# STM32_ACTUADORES.net
KiCad netlist of a schematic drawn in EAGLE
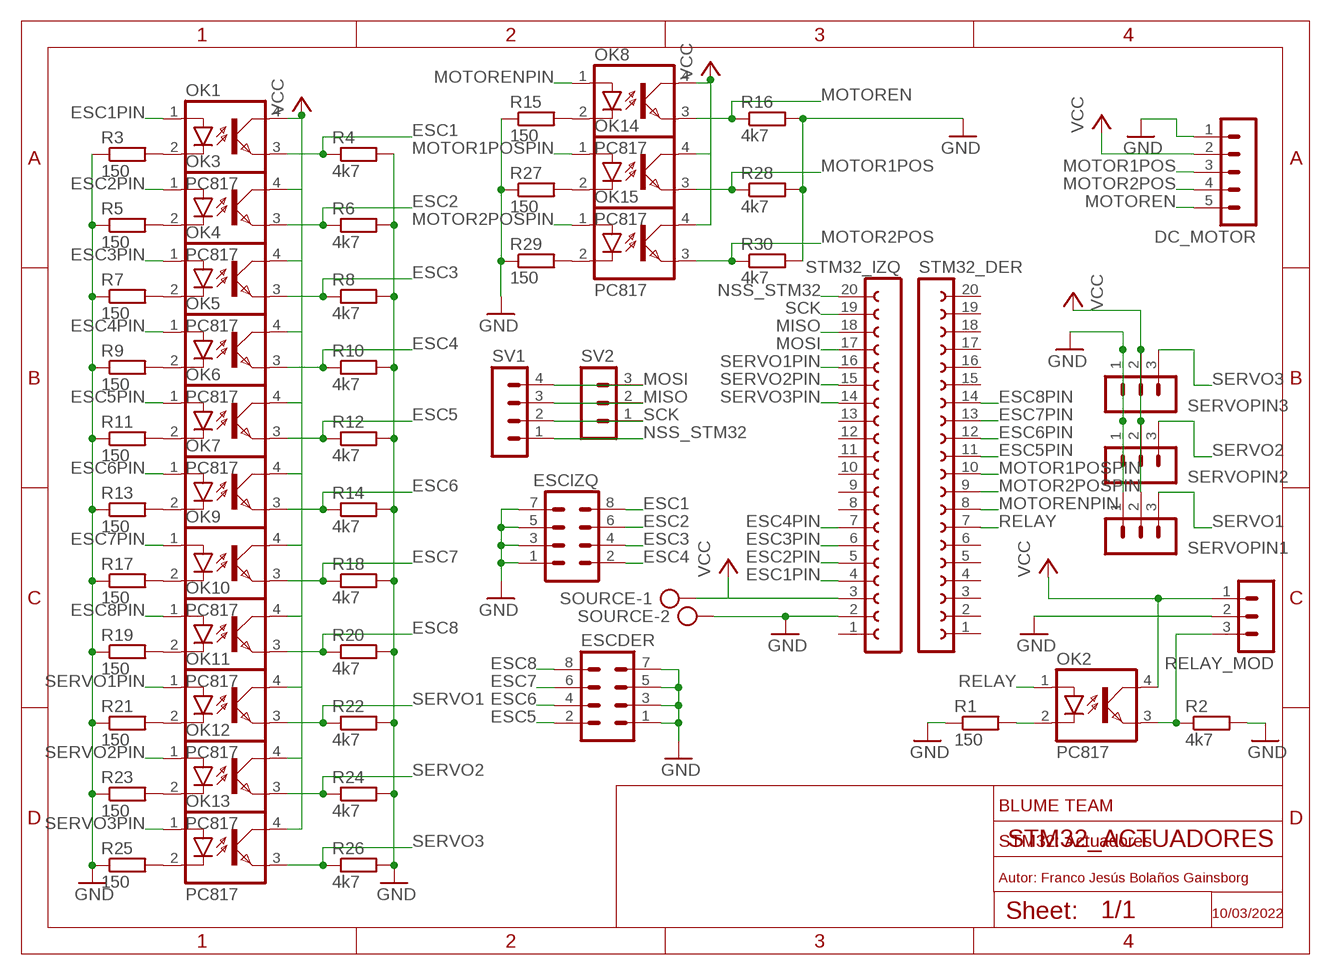
[diagram p0: schematic, sheet 1]

(export (version "E")
  (design (tool "Eeschema 10.0.6"))
  (components
    (comp (ref "DC_MOTOR")
      (value "MA05-1")
      (footprint "eagle-import:MA05-1")
      (libsource (lib "eagle-import") (part "MA05-1"))
    )
    (comp (ref "ESCDER")
      (value "MA04-2")
      (footprint "eagle-import:MA04-2")
      (libsource (lib "eagle-import") (part "MA04-2"))
    )
    (comp (ref "ESCIZQ")
      (value "MA04-2")
      (footprint "eagle-import:MA04-2")
      (libsource (lib "eagle-import") (part "MA04-2"))
    )
    (comp (ref "OK1")
      (value "PC817")
      (footprint "eagle-import:DIL04")
      (fields (field (name "MPN") "PC817X4J000F"))
      (libsource (lib "eagle-import") (part "PC817"))
    )
    (comp (ref "OK2")
      (value "PC817")
      (footprint "eagle-import:DIL04")
      (fields (field (name "MPN") "PC817X4J000F"))
      (libsource (lib "eagle-import") (part "PC817"))
    )
    (comp (ref "OK3")
      (value "PC817")
      (footprint "eagle-import:DIL04")
      (fields (field (name "MPN") "PC817X4J000F"))
      (libsource (lib "eagle-import") (part "PC817"))
    )
    (comp (ref "OK4")
      (value "PC817")
      (footprint "eagle-import:DIL04")
      (fields (field (name "MPN") "PC817X4J000F"))
      (libsource (lib "eagle-import") (part "PC817"))
    )
    (comp (ref "OK5")
      (value "PC817")
      (footprint "eagle-import:DIL04")
      (fields (field (name "MPN") "PC817X4J000F"))
      (libsource (lib "eagle-import") (part "PC817"))
    )
    (comp (ref "OK6")
      (value "PC817")
      (footprint "eagle-import:DIL04")
      (fields (field (name "MPN") "PC817X4J000F"))
      (libsource (lib "eagle-import") (part "PC817"))
    )
    (comp (ref "OK7")
      (value "PC817")
      (footprint "eagle-import:DIL04")
      (fields (field (name "MPN") "PC817X4J000F"))
      (libsource (lib "eagle-import") (part "PC817"))
    )
    (comp (ref "OK8")
      (value "PC817")
      (footprint "eagle-import:DIL04")
      (fields (field (name "MPN") "PC817X4J000F"))
      (libsource (lib "eagle-import") (part "PC817"))
    )
    (comp (ref "OK9")
      (value "PC817")
      (footprint "eagle-import:DIL04")
      (fields (field (name "MPN") "PC817X4J000F"))
      (libsource (lib "eagle-import") (part "PC817"))
    )
    (comp (ref "OK10")
      (value "PC817")
      (footprint "eagle-import:DIL04")
      (fields (field (name "MPN") "PC817X4J000F"))
      (libsource (lib "eagle-import") (part "PC817"))
    )
    (comp (ref "OK11")
      (value "PC817")
      (footprint "eagle-import:DIL04")
      (fields (field (name "MPN") "PC817X4J000F"))
      (libsource (lib "eagle-import") (part "PC817"))
    )
    (comp (ref "OK12")
      (value "PC817")
      (footprint "eagle-import:DIL04")
      (fields (field (name "MPN") "PC817X4J000F"))
      (libsource (lib "eagle-import") (part "PC817"))
    )
    (comp (ref "OK13")
      (value "PC817")
      (footprint "eagle-import:DIL04")
      (fields (field (name "MPN") "PC817X4J000F"))
      (libsource (lib "eagle-import") (part "PC817"))
    )
    (comp (ref "OK14")
      (value "PC817")
      (footprint "eagle-import:DIL04")
      (fields (field (name "MPN") "PC817X4J000F"))
      (libsource (lib "eagle-import") (part "PC817"))
    )
    (comp (ref "OK15")
      (value "PC817")
      (footprint "eagle-import:DIL04")
      (fields (field (name "MPN") "PC817X4J000F"))
      (libsource (lib "eagle-import") (part "PC817"))
    )
    (comp (ref "R1")
      (value "150")
      (footprint "eagle-import:0207_10")
      (libsource (lib "eagle-import") (part "R-EU_0207/10"))
    )
    (comp (ref "R2")
      (value "4k7")
      (footprint "eagle-import:0207_10")
      (libsource (lib "eagle-import") (part "R-EU_0207/10"))
    )
    (comp (ref "R3")
      (value "150")
      (footprint "eagle-import:0207_10")
      (libsource (lib "eagle-import") (part "R-EU_0207/10"))
    )
    (comp (ref "R4")
      (value "4k7")
      (footprint "eagle-import:0207_10")
      (libsource (lib "eagle-import") (part "R-EU_0207/10"))
    )
    (comp (ref "R5")
      (value "150")
      (footprint "eagle-import:0207_10")
      (libsource (lib "eagle-import") (part "R-EU_0207/10"))
    )
    (comp (ref "R6")
      (value "4k7")
      (footprint "eagle-import:0207_10")
      (libsource (lib "eagle-import") (part "R-EU_0207/10"))
    )
    (comp (ref "R7")
      (value "150")
      (footprint "eagle-import:0207_10")
      (libsource (lib "eagle-import") (part "R-EU_0207/10"))
    )
    (comp (ref "R8")
      (value "4k7")
      (footprint "eagle-import:0207_10")
      (libsource (lib "eagle-import") (part "R-EU_0207/10"))
    )
    (comp (ref "R9")
      (value "150")
      (footprint "eagle-import:0207_10")
      (libsource (lib "eagle-import") (part "R-EU_0207/10"))
    )
    (comp (ref "R10")
      (value "4k7")
      (footprint "eagle-import:0207_10")
      (libsource (lib "eagle-import") (part "R-EU_0207/10"))
    )
    (comp (ref "R11")
      (value "150")
      (footprint "eagle-import:0207_10")
      (libsource (lib "eagle-import") (part "R-EU_0207/10"))
    )
    (comp (ref "R12")
      (value "4k7")
      (footprint "eagle-import:0207_10")
      (libsource (lib "eagle-import") (part "R-EU_0207/10"))
    )
    (comp (ref "R13")
      (value "150")
      (footprint "eagle-import:0207_10")
      (libsource (lib "eagle-import") (part "R-EU_0207/10"))
    )
    (comp (ref "R14")
      (value "4k7")
      (footprint "eagle-import:0207_10")
      (libsource (lib "eagle-import") (part "R-EU_0207/10"))
    )
    (comp (ref "R15")
      (value "150")
      (footprint "eagle-import:0207_10")
      (libsource (lib "eagle-import") (part "R-EU_0207/10"))
    )
    (comp (ref "R16")
      (value "4k7")
      (footprint "eagle-import:0207_10")
      (libsource (lib "eagle-import") (part "R-EU_0207/10"))
    )
    (comp (ref "R17")
      (value "150")
      (footprint "eagle-import:0207_10")
      (libsource (lib "eagle-import") (part "R-EU_0207/10"))
    )
    (comp (ref "R18")
      (value "4k7")
      (footprint "eagle-import:0207_10")
      (libsource (lib "eagle-import") (part "R-EU_0207/10"))
    )
    (comp (ref "R19")
      (value "150")
      (footprint "eagle-import:0207_10")
      (libsource (lib "eagle-import") (part "R-EU_0207/10"))
    )
    (comp (ref "R20")
      (value "4k7")
      (footprint "eagle-import:0207_10")
      (libsource (lib "eagle-import") (part "R-EU_0207/10"))
    )
    (comp (ref "R21")
      (value "150")
      (footprint "eagle-import:0207_10")
      (libsource (lib "eagle-import") (part "R-EU_0207/10"))
    )
    (comp (ref "R22")
      (value "4k7")
      (footprint "eagle-import:0207_10")
      (libsource (lib "eagle-import") (part "R-EU_0207/10"))
    )
    (comp (ref "R23")
      (value "150")
      (footprint "eagle-import:0207_10")
      (libsource (lib "eagle-import") (part "R-EU_0207/10"))
    )
    (comp (ref "R24")
      (value "4k7")
      (footprint "eagle-import:0207_10")
      (libsource (lib "eagle-import") (part "R-EU_0207/10"))
    )
    (comp (ref "R25")
      (value "150")
      (footprint "eagle-import:0207_10")
      (libsource (lib "eagle-import") (part "R-EU_0207/10"))
    )
    (comp (ref "R26")
      (value "4k7")
      (footprint "eagle-import:0207_10")
      (libsource (lib "eagle-import") (part "R-EU_0207/10"))
    )
    (comp (ref "R27")
      (value "150")
      (footprint "eagle-import:0207_10")
      (libsource (lib "eagle-import") (part "R-EU_0207/10"))
    )
    (comp (ref "R28")
      (value "4k7")
      (footprint "eagle-import:0207_10")
      (libsource (lib "eagle-import") (part "R-EU_0207/10"))
    )
    (comp (ref "R29")
      (value "150")
      (footprint "eagle-import:0207_10")
      (libsource (lib "eagle-import") (part "R-EU_0207/10"))
    )
    (comp (ref "R30")
      (value "4k7")
      (footprint "eagle-import:0207_10")
      (libsource (lib "eagle-import") (part "R-EU_0207/10"))
    )
    (comp (ref "RELAY_MOD")
      (value "MA03-1")
      (footprint "eagle-import:MA03-1")
      (libsource (lib "eagle-import") (part "MA03-1"))
    )
    (comp (ref "SERVOPIN1")
      (value "MA03-1")
      (footprint "eagle-import:MA03-1")
      (libsource (lib "eagle-import") (part "MA03-1"))
    )
    (comp (ref "SERVOPIN2")
      (value "MA03-1")
      (footprint "eagle-import:MA03-1")
      (libsource (lib "eagle-import") (part "MA03-1"))
    )
    (comp (ref "SERVOPIN3")
      (value "MA03-1")
      (footprint "eagle-import:MA03-1")
      (libsource (lib "eagle-import") (part "MA03-1"))
    )
    (comp (ref "SOURCE")
      (value "AK300/2")
      (footprint "eagle-import:AK300_2")
      (libsource (lib "eagle-import") (part "AK300/2"))
    )
    (comp (ref "STM32_DER")
      (value "FE20-1")
      (footprint "eagle-import:FE20")
      (libsource (lib "eagle-import") (part "FE20-1"))
    )
    (comp (ref "STM32_IZQ")
      (value "FE20-1")
      (footprint "eagle-import:FE20")
      (libsource (lib "eagle-import") (part "FE20-1"))
    )
    (comp (ref "SV1")
      (value "MA04-1")
      (footprint "eagle-import:MA04-1")
      (libsource (lib "eagle-import") (part "MA04-1"))
    )
    (comp (ref "SV2")
      (value "MA03-1")
      (footprint "eagle-import:MA03-1")
      (libsource (lib "eagle-import") (part "MA03-1"))
    )
  )
  (nets
    (net (code "1") (name "/ESC1") (class "Default")
      (node (ref "ESCIZQ") (pin "8") (pinfunction "8_8") (pintype "passive"))
      (node (ref "OK1") (pin "3") (pinfunction "EMIT_3") (pintype "passive"))
      (node (ref "R4") (pin "1") (pinfunction "1_1") (pintype "passive"))
    )
    (net (code "2") (name "/ESC1PIN") (class "Default")
      (node (ref "OK1") (pin "1") (pinfunction "A_1") (pintype "passive"))
      (node (ref "STM32_IZQ") (pin "4") (pinfunction "4_4") (pintype "passive"))
    )
    (net (code "3") (name "/ESC2") (class "Default")
      (node (ref "ESCIZQ") (pin "6") (pinfunction "6_6") (pintype "passive"))
      (node (ref "OK3") (pin "3") (pinfunction "EMIT_3") (pintype "passive"))
      (node (ref "R6") (pin "1") (pinfunction "1_1") (pintype "passive"))
    )
    (net (code "4") (name "/ESC2PIN") (class "Default")
      (node (ref "OK3") (pin "1") (pinfunction "A_1") (pintype "passive"))
      (node (ref "STM32_IZQ") (pin "5") (pinfunction "5_5") (pintype "passive"))
    )
    (net (code "5") (name "/ESC3") (class "Default")
      (node (ref "ESCIZQ") (pin "4") (pinfunction "4_4") (pintype "passive"))
      (node (ref "OK4") (pin "3") (pinfunction "EMIT_3") (pintype "passive"))
      (node (ref "R8") (pin "1") (pinfunction "1_1") (pintype "passive"))
    )
    (net (code "6") (name "/ESC3PIN") (class "Default")
      (node (ref "OK4") (pin "1") (pinfunction "A_1") (pintype "passive"))
      (node (ref "STM32_IZQ") (pin "6") (pinfunction "6_6") (pintype "passive"))
    )
    (net (code "7") (name "/ESC4") (class "Default")
      (node (ref "ESCIZQ") (pin "2") (pinfunction "2_2") (pintype "passive"))
      (node (ref "OK5") (pin "3") (pinfunction "EMIT_3") (pintype "passive"))
      (node (ref "R10") (pin "1") (pinfunction "1_1") (pintype "passive"))
    )
    (net (code "8") (name "/ESC4PIN") (class "Default")
      (node (ref "OK5") (pin "1") (pinfunction "A_1") (pintype "passive"))
      (node (ref "STM32_IZQ") (pin "7") (pinfunction "7_7") (pintype "passive"))
    )
    (net (code "9") (name "/ESC5") (class "Default")
      (node (ref "ESCDER") (pin "2") (pinfunction "2_2") (pintype "passive"))
      (node (ref "OK6") (pin "3") (pinfunction "EMIT_3") (pintype "passive"))
      (node (ref "R12") (pin "1") (pinfunction "1_1") (pintype "passive"))
    )
    (net (code "10") (name "/ESC5PIN") (class "Default")
      (node (ref "OK6") (pin "1") (pinfunction "A_1") (pintype "passive"))
      (node (ref "STM32_DER") (pin "11") (pinfunction "11_11") (pintype "passive"))
    )
    (net (code "11") (name "/ESC6") (class "Default")
      (node (ref "ESCDER") (pin "4") (pinfunction "4_4") (pintype "passive"))
      (node (ref "OK7") (pin "3") (pinfunction "EMIT_3") (pintype "passive"))
      (node (ref "R14") (pin "1") (pinfunction "1_1") (pintype "passive"))
    )
    (net (code "12") (name "/ESC6PIN") (class "Default")
      (node (ref "OK7") (pin "1") (pinfunction "A_1") (pintype "passive"))
      (node (ref "STM32_DER") (pin "12") (pinfunction "12_12") (pintype "passive"))
    )
    (net (code "13") (name "/ESC7") (class "Default")
      (node (ref "ESCDER") (pin "6") (pinfunction "6_6") (pintype "passive"))
      (node (ref "OK9") (pin "3") (pinfunction "EMIT_3") (pintype "passive"))
      (node (ref "R18") (pin "1") (pinfunction "1_1") (pintype "passive"))
    )
    (net (code "14") (name "/ESC7PIN") (class "Default")
      (node (ref "OK9") (pin "1") (pinfunction "A_1") (pintype "passive"))
      (node (ref "STM32_DER") (pin "13") (pinfunction "13_13") (pintype "passive"))
    )
    (net (code "15") (name "/ESC8") (class "Default")
      (node (ref "ESCDER") (pin "8") (pinfunction "8_8") (pintype "passive"))
      (node (ref "OK10") (pin "3") (pinfunction "EMIT_3") (pintype "passive"))
      (node (ref "R20") (pin "1") (pinfunction "1_1") (pintype "passive"))
    )
    (net (code "16") (name "/ESC8PIN") (class "Default")
      (node (ref "OK10") (pin "1") (pinfunction "A_1") (pintype "passive"))
      (node (ref "STM32_DER") (pin "14") (pinfunction "14_14") (pintype "passive"))
    )
    (net (code "17") (name "/MISO") (class "Default")
      (node (ref "STM32_IZQ") (pin "18") (pinfunction "18_18") (pintype "passive"))
      (node (ref "SV1") (pin "3") (pinfunction "3_3") (pintype "passive"))
      (node (ref "SV2") (pin "2") (pinfunction "2_2") (pintype "passive"))
    )
    (net (code "18") (name "/MOSI") (class "Default")
      (node (ref "STM32_IZQ") (pin "17") (pinfunction "17_17") (pintype "passive"))
      (node (ref "SV1") (pin "4") (pinfunction "4_4") (pintype "passive"))
      (node (ref "SV2") (pin "3") (pinfunction "3_3") (pintype "passive"))
    )
    (net (code "19") (name "/MOTOR1POS") (class "Default")
      (node (ref "DC_MOTOR") (pin "3") (pinfunction "3_3") (pintype "passive"))
      (node (ref "OK14") (pin "3") (pinfunction "EMIT_3") (pintype "passive"))
      (node (ref "R28") (pin "1") (pinfunction "1_1") (pintype "passive"))
    )
    (net (code "20") (name "/MOTOR1POSPIN") (class "Default")
      (node (ref "OK14") (pin "1") (pinfunction "A_1") (pintype "passive"))
      (node (ref "STM32_DER") (pin "10") (pinfunction "10_10") (pintype "passive"))
    )
    (net (code "21") (name "/MOTOR2POS") (class "Default")
      (node (ref "DC_MOTOR") (pin "4") (pinfunction "4_4") (pintype "passive"))
      (node (ref "OK15") (pin "3") (pinfunction "EMIT_3") (pintype "passive"))
      (node (ref "R30") (pin "1") (pinfunction "1_1") (pintype "passive"))
    )
    (net (code "22") (name "/MOTOR2POSPIN") (class "Default")
      (node (ref "OK15") (pin "1") (pinfunction "A_1") (pintype "passive"))
      (node (ref "STM32_DER") (pin "9") (pinfunction "9_9") (pintype "passive"))
    )
    (net (code "23") (name "/MOTOREN") (class "Default")
      (node (ref "DC_MOTOR") (pin "5") (pinfunction "5_5") (pintype "passive"))
      (node (ref "OK8") (pin "3") (pinfunction "EMIT_3") (pintype "passive"))
      (node (ref "R16") (pin "1") (pinfunction "1_1") (pintype "passive"))
    )
    (net (code "24") (name "/MOTORENPIN") (class "Default")
      (node (ref "OK8") (pin "1") (pinfunction "A_1") (pintype "passive"))
      (node (ref "STM32_DER") (pin "8") (pinfunction "8_8") (pintype "passive"))
    )
    (net (code "25") (name "/NSS_STM32") (class "Default")
      (node (ref "STM32_IZQ") (pin "20") (pinfunction "20_20") (pintype "passive"))
      (node (ref "SV1") (pin "1") (pinfunction "1_1") (pintype "passive"))
    )
    (net (code "26") (name "/RELAY") (class "Default")
      (node (ref "OK2") (pin "1") (pinfunction "A_1") (pintype "passive"))
      (node (ref "STM32_DER") (pin "7") (pinfunction "7_7") (pintype "passive"))
    )
    (net (code "27") (name "/SCK") (class "Default")
      (node (ref "STM32_IZQ") (pin "19") (pinfunction "19_19") (pintype "passive"))
      (node (ref "SV1") (pin "2") (pinfunction "2_2") (pintype "passive"))
      (node (ref "SV2") (pin "1") (pinfunction "1_1") (pintype "passive"))
    )
    (net (code "28") (name "/SERVO1") (class "Default")
      (node (ref "OK11") (pin "3") (pinfunction "EMIT_3") (pintype "passive"))
      (node (ref "R22") (pin "1") (pinfunction "1_1") (pintype "passive"))
      (node (ref "SERVOPIN1") (pin "3") (pinfunction "3_3") (pintype "passive"))
    )
    (net (code "29") (name "/SERVO1PIN") (class "Default")
      (node (ref "OK11") (pin "1") (pinfunction "A_1") (pintype "passive"))
      (node (ref "STM32_IZQ") (pin "16") (pinfunction "16_16") (pintype "passive"))
    )
    (net (code "30") (name "/SERVO2") (class "Default")
      (node (ref "OK12") (pin "3") (pinfunction "EMIT_3") (pintype "passive"))
      (node (ref "R24") (pin "1") (pinfunction "1_1") (pintype "passive"))
      (node (ref "SERVOPIN2") (pin "3") (pinfunction "3_3") (pintype "passive"))
    )
    (net (code "31") (name "/SERVO2PIN") (class "Default")
      (node (ref "OK12") (pin "1") (pinfunction "A_1") (pintype "passive"))
      (node (ref "STM32_IZQ") (pin "15") (pinfunction "15_15") (pintype "passive"))
    )
    (net (code "32") (name "/SERVO3") (class "Default")
      (node (ref "OK13") (pin "3") (pinfunction "EMIT_3") (pintype "passive"))
      (node (ref "R26") (pin "1") (pinfunction "1_1") (pintype "passive"))
      (node (ref "SERVOPIN3") (pin "3") (pinfunction "3_3") (pintype "passive"))
    )
    (net (code "33") (name "/SERVO3PIN") (class "Default")
      (node (ref "OK13") (pin "1") (pinfunction "A_1") (pintype "passive"))
      (node (ref "STM32_IZQ") (pin "14") (pinfunction "14_14") (pintype "passive"))
    )
    (net (code "34") (name "GND") (class "Default")
      (node (ref "DC_MOTOR") (pin "1") (pinfunction "1_1") (pintype "passive"))
      (node (ref "ESCDER") (pin "1") (pinfunction "1_1") (pintype "passive"))
      (node (ref "ESCDER") (pin "3") (pinfunction "3_3") (pintype "passive"))
      (node (ref "ESCDER") (pin "5") (pinfunction "5_5") (pintype "passive"))
      (node (ref "ESCDER") (pin "7") (pinfunction "7_7") (pintype "passive"))
      (node (ref "ESCIZQ") (pin "1") (pinfunction "1_1") (pintype "passive"))
      (node (ref "ESCIZQ") (pin "3") (pinfunction "3_3") (pintype "passive"))
      (node (ref "ESCIZQ") (pin "5") (pinfunction "5_5") (pintype "passive"))
      (node (ref "ESCIZQ") (pin "7") (pinfunction "7_7") (pintype "passive"))
      (node (ref "R1") (pin "1") (pinfunction "1_1") (pintype "passive"))
      (node (ref "R10") (pin "2") (pinfunction "2_2") (pintype "passive"))
      (node (ref "R11") (pin "1") (pinfunction "1_1") (pintype "passive"))
      (node (ref "R12") (pin "2") (pinfunction "2_2") (pintype "passive"))
      (node (ref "R13") (pin "1") (pinfunction "1_1") (pintype "passive"))
      (node (ref "R14") (pin "2") (pinfunction "2_2") (pintype "passive"))
      (node (ref "R15") (pin "1") (pinfunction "1_1") (pintype "passive"))
      (node (ref "R16") (pin "2") (pinfunction "2_2") (pintype "passive"))
      (node (ref "R17") (pin "1") (pinfunction "1_1") (pintype "passive"))
      (node (ref "R18") (pin "2") (pinfunction "2_2") (pintype "passive"))
      (node (ref "R19") (pin "1") (pinfunction "1_1") (pintype "passive"))
      (node (ref "R2") (pin "2") (pinfunction "2_2") (pintype "passive"))
      (node (ref "R20") (pin "2") (pinfunction "2_2") (pintype "passive"))
      (node (ref "R21") (pin "1") (pinfunction "1_1") (pintype "passive"))
      (node (ref "R22") (pin "2") (pinfunction "2_2") (pintype "passive"))
      (node (ref "R23") (pin "1") (pinfunction "1_1") (pintype "passive"))
      (node (ref "R24") (pin "2") (pinfunction "2_2") (pintype "passive"))
      (node (ref "R25") (pin "1") (pinfunction "1_1") (pintype "passive"))
      (node (ref "R26") (pin "2") (pinfunction "2_2") (pintype "passive"))
      (node (ref "R27") (pin "1") (pinfunction "1_1") (pintype "passive"))
      (node (ref "R28") (pin "2") (pinfunction "2_2") (pintype "passive"))
      (node (ref "R29") (pin "1") (pinfunction "1_1") (pintype "passive"))
      (node (ref "R3") (pin "1") (pinfunction "1_1") (pintype "passive"))
      (node (ref "R30") (pin "2") (pinfunction "2_2") (pintype "passive"))
      (node (ref "R4") (pin "2") (pinfunction "2_2") (pintype "passive"))
      (node (ref "R5") (pin "1") (pinfunction "1_1") (pintype "passive"))
      (node (ref "R6") (pin "2") (pinfunction "2_2") (pintype "passive"))
      (node (ref "R7") (pin "1") (pinfunction "1_1") (pintype "passive"))
      (node (ref "R8") (pin "2") (pinfunction "2_2") (pintype "passive"))
      (node (ref "R9") (pin "1") (pinfunction "1_1") (pintype "passive"))
      (node (ref "RELAY_MOD") (pin "2") (pinfunction "2_2") (pintype "passive"))
      (node (ref "SERVOPIN1") (pin "1") (pinfunction "1_1") (pintype "passive"))
      (node (ref "SERVOPIN2") (pin "1") (pinfunction "1_1") (pintype "passive"))
      (node (ref "SERVOPIN3") (pin "1") (pinfunction "1_1") (pintype "passive"))
      (node (ref "SOURCE") (pin "2") (pinfunction "KL_2") (pintype "passive"))
      (node (ref "STM32_IZQ") (pin "2") (pinfunction "2_2") (pintype "passive"))
    )
    (net (code "35") (name "Net-(OK1-C)") (class "Default")
      (node (ref "OK1") (pin "2") (pinfunction "C_2") (pintype "passive"))
      (node (ref "R3") (pin "2") (pinfunction "2_2") (pintype "passive"))
    )
    (net (code "36") (name "Net-(OK2-C)") (class "Default")
      (node (ref "OK2") (pin "2") (pinfunction "C_2") (pintype "passive"))
      (node (ref "R1") (pin "2") (pinfunction "2_2") (pintype "passive"))
    )
    (net (code "37") (name "Net-(OK2-EMIT)") (class "Default")
      (node (ref "OK2") (pin "3") (pinfunction "EMIT_3") (pintype "passive"))
      (node (ref "R2") (pin "1") (pinfunction "1_1") (pintype "passive"))
      (node (ref "RELAY_MOD") (pin "3") (pinfunction "3_3") (pintype "passive"))
    )
    (net (code "38") (name "Net-(OK3-C)") (class "Default")
      (node (ref "OK3") (pin "2") (pinfunction "C_2") (pintype "passive"))
      (node (ref "R5") (pin "2") (pinfunction "2_2") (pintype "passive"))
    )
    (net (code "39") (name "Net-(OK4-C)") (class "Default")
      (node (ref "OK4") (pin "2") (pinfunction "C_2") (pintype "passive"))
      (node (ref "R7") (pin "2") (pinfunction "2_2") (pintype "passive"))
    )
    (net (code "40") (name "Net-(OK5-C)") (class "Default")
      (node (ref "OK5") (pin "2") (pinfunction "C_2") (pintype "passive"))
      (node (ref "R9") (pin "2") (pinfunction "2_2") (pintype "passive"))
    )
    (net (code "41") (name "Net-(OK6-C)") (class "Default")
      (node (ref "OK6") (pin "2") (pinfunction "C_2") (pintype "passive"))
      (node (ref "R11") (pin "2") (pinfunction "2_2") (pintype "passive"))
    )
    (net (code "42") (name "Net-(OK7-C)") (class "Default")
      (node (ref "OK7") (pin "2") (pinfunction "C_2") (pintype "passive"))
      (node (ref "R13") (pin "2") (pinfunction "2_2") (pintype "passive"))
    )
    (net (code "43") (name "Net-(OK8-C)") (class "Default")
      (node (ref "OK8") (pin "2") (pinfunction "C_2") (pintype "passive"))
      (node (ref "R15") (pin "2") (pinfunction "2_2") (pintype "passive"))
    )
    (net (code "44") (name "Net-(OK9-C)") (class "Default")
      (node (ref "OK9") (pin "2") (pinfunction "C_2") (pintype "passive"))
      (node (ref "R17") (pin "2") (pinfunction "2_2") (pintype "passive"))
    )
    (net (code "45") (name "Net-(OK10-C)") (class "Default")
      (node (ref "OK10") (pin "2") (pinfunction "C_2") (pintype "passive"))
      (node (ref "R19") (pin "2") (pinfunction "2_2") (pintype "passive"))
    )
    (net (code "46") (name "Net-(OK11-C)") (class "Default")
      (node (ref "OK11") (pin "2") (pinfunction "C_2") (pintype "passive"))
      (node (ref "R21") (pin "2") (pinfunction "2_2") (pintype "passive"))
    )
    (net (code "47") (name "Net-(OK12-C)") (class "Default")
      (node (ref "OK12") (pin "2") (pinfunction "C_2") (pintype "passive"))
      (node (ref "R23") (pin "2") (pinfunction "2_2") (pintype "passive"))
    )
    (net (code "48") (name "Net-(OK13-C)") (class "Default")
      (node (ref "OK13") (pin "2") (pinfunction "C_2") (pintype "passive"))
      (node (ref "R25") (pin "2") (pinfunction "2_2") (pintype "passive"))
    )
    (net (code "49") (name "Net-(OK14-C)") (class "Default")
      (node (ref "OK14") (pin "2") (pinfunction "C_2") (pintype "passive"))
      (node (ref "R27") (pin "2") (pinfunction "2_2") (pintype "passive"))
    )
    (net (code "50") (name "Net-(OK15-C)") (class "Default")
      (node (ref "OK15") (pin "2") (pinfunction "C_2") (pintype "passive"))
      (node (ref "R29") (pin "2") (pinfunction "2_2") (pintype "passive"))
    )
    (net (code "51") (name "VCC") (class "Default")
      (node (ref "DC_MOTOR") (pin "2") (pinfunction "2_2") (pintype "passive"))
      (node (ref "OK1") (pin "4") (pinfunction "COL_4") (pintype "passive"))
      (node (ref "OK10") (pin "4") (pinfunction "COL_4") (pintype "passive"))
      (node (ref "OK11") (pin "4") (pinfunction "COL_4") (pintype "passive"))
      (node (ref "OK12") (pin "4") (pinfunction "COL_4") (pintype "passive"))
      (node (ref "OK13") (pin "4") (pinfunction "COL_4") (pintype "passive"))
      (node (ref "OK14") (pin "4") (pinfunction "COL_4") (pintype "passive"))
      (node (ref "OK15") (pin "4") (pinfunction "COL_4") (pintype "passive"))
      (node (ref "OK2") (pin "4") (pinfunction "COL_4") (pintype "passive"))
      (node (ref "OK3") (pin "4") (pinfunction "COL_4") (pintype "passive"))
      (node (ref "OK4") (pin "4") (pinfunction "COL_4") (pintype "passive"))
      (node (ref "OK5") (pin "4") (pinfunction "COL_4") (pintype "passive"))
      (node (ref "OK6") (pin "4") (pinfunction "COL_4") (pintype "passive"))
      (node (ref "OK7") (pin "4") (pinfunction "COL_4") (pintype "passive"))
      (node (ref "OK8") (pin "4") (pinfunction "COL_4") (pintype "passive"))
      (node (ref "OK9") (pin "4") (pinfunction "COL_4") (pintype "passive"))
      (node (ref "RELAY_MOD") (pin "1") (pinfunction "1_1") (pintype "passive"))
      (node (ref "SERVOPIN1") (pin "2") (pinfunction "2_2") (pintype "passive"))
      (node (ref "SERVOPIN2") (pin "2") (pinfunction "2_2") (pintype "passive"))
      (node (ref "SERVOPIN3") (pin "2") (pinfunction "2_2") (pintype "passive"))
      (node (ref "SOURCE") (pin "1") (pinfunction "KL_1") (pintype "passive"))
      (node (ref "STM32_IZQ") (pin "3") (pinfunction "3_3") (pintype "passive"))
    )
    (net (code "52") (name "unconnected-(STM32_DER-Pad1)") (class "Default")
      (node (ref "STM32_DER") (pin "1") (pinfunction "1_1") (pintype "passive"))
    )
    (net (code "53") (name "unconnected-(STM32_DER-Pad2)") (class "Default")
      (node (ref "STM32_DER") (pin "2") (pinfunction "2_2") (pintype "passive"))
    )
    (net (code "54") (name "unconnected-(STM32_DER-Pad3)") (class "Default")
      (node (ref "STM32_DER") (pin "3") (pinfunction "3_3") (pintype "passive"))
    )
    (net (code "55") (name "unconnected-(STM32_DER-Pad4)") (class "Default")
      (node (ref "STM32_DER") (pin "4") (pinfunction "4_4") (pintype "passive"))
    )
    (net (code "56") (name "unconnected-(STM32_DER-Pad5)") (class "Default")
      (node (ref "STM32_DER") (pin "5") (pinfunction "5_5") (pintype "passive"))
    )
    (net (code "57") (name "unconnected-(STM32_DER-Pad6)") (class "Default")
      (node (ref "STM32_DER") (pin "6") (pinfunction "6_6") (pintype "passive"))
    )
    (net (code "58") (name "unconnected-(STM32_DER-Pad15)") (class "Default")
      (node (ref "STM32_DER") (pin "15") (pinfunction "15_15") (pintype "passive"))
    )
    (net (code "59") (name "unconnected-(STM32_DER-Pad16)") (class "Default")
      (node (ref "STM32_DER") (pin "16") (pinfunction "16_16") (pintype "passive"))
    )
    (net (code "60") (name "unconnected-(STM32_DER-Pad17)") (class "Default")
      (node (ref "STM32_DER") (pin "17") (pinfunction "17_17") (pintype "passive"))
    )
    (net (code "61") (name "unconnected-(STM32_DER-Pad18)") (class "Default")
      (node (ref "STM32_DER") (pin "18") (pinfunction "18_18") (pintype "passive"))
    )
    (net (code "62") (name "unconnected-(STM32_DER-Pad19)") (class "Default")
      (node (ref "STM32_DER") (pin "19") (pinfunction "19_19") (pintype "passive"))
    )
    (net (code "63") (name "unconnected-(STM32_DER-Pad20)") (class "Default")
      (node (ref "STM32_DER") (pin "20") (pinfunction "20_20") (pintype "passive"))
    )
    (net (code "64") (name "unconnected-(STM32_IZQ-Pad1)") (class "Default")
      (node (ref "STM32_IZQ") (pin "1") (pinfunction "1_1") (pintype "passive"))
    )
    (net (code "65") (name "unconnected-(STM32_IZQ-Pad8)") (class "Default")
      (node (ref "STM32_IZQ") (pin "8") (pinfunction "8_8") (pintype "passive"))
    )
    (net (code "66") (name "unconnected-(STM32_IZQ-Pad9)") (class "Default")
      (node (ref "STM32_IZQ") (pin "9") (pinfunction "9_9") (pintype "passive"))
    )
    (net (code "67") (name "unconnected-(STM32_IZQ-Pad10)") (class "Default")
      (node (ref "STM32_IZQ") (pin "10") (pinfunction "10_10") (pintype "passive"))
    )
    (net (code "68") (name "unconnected-(STM32_IZQ-Pad11)") (class "Default")
      (node (ref "STM32_IZQ") (pin "11") (pinfunction "11_11") (pintype "passive"))
    )
    (net (code "69") (name "unconnected-(STM32_IZQ-Pad12)") (class "Default")
      (node (ref "STM32_IZQ") (pin "12") (pinfunction "12_12") (pintype "passive"))
    )
    (net (code "70") (name "unconnected-(STM32_IZQ-Pad13)") (class "Default")
      (node (ref "STM32_IZQ") (pin "13") (pinfunction "13_13") (pintype "passive"))
    )
  )
)
